# AudioMega_HaGeHa_SMD_v101.net
KiCad netlist of a schematic drawn in EAGLE
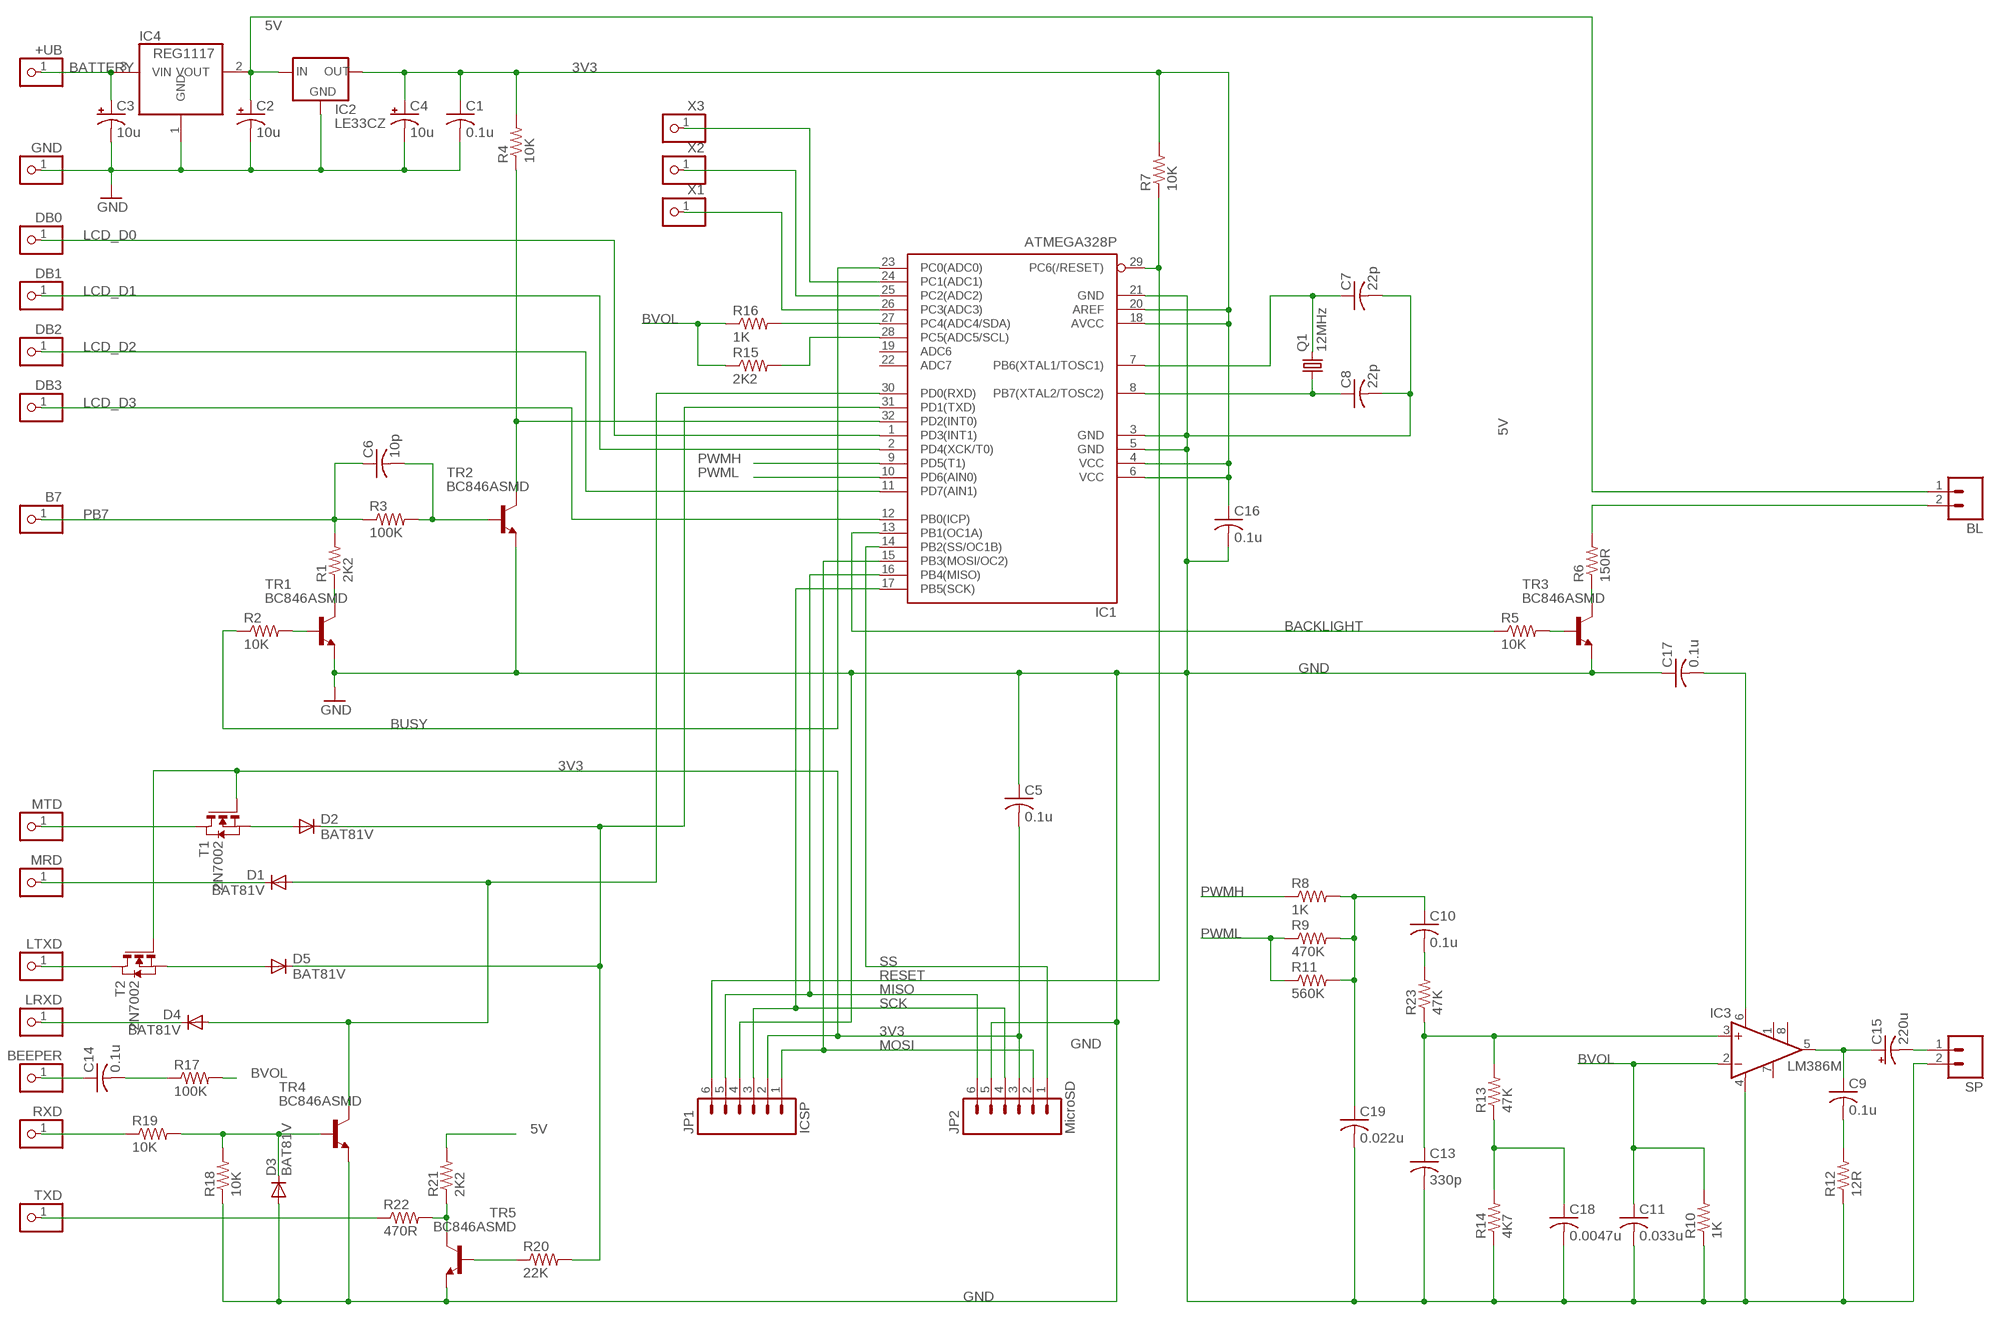
[diagram p0: schematic, sheet 1]

(export (version "E")
  (design (tool "Eeschema 10.0.6"))
  (components
    (comp (ref "+UB")
      (value "PINHD-1X1")
      (footprint "eagle-import:1X01")
      (libsource (lib "eagle-import") (part "PINHD-1X1"))
    )
    (comp (ref "B7")
      (value "PINHD-1X1")
      (footprint "eagle-import:1X01")
      (libsource (lib "eagle-import") (part "PINHD-1X1"))
    )
    (comp (ref "BEEPER")
      (value "PINHD-1X1")
      (footprint "eagle-import:1X01")
      (libsource (lib "eagle-import") (part "PINHD-1X1"))
    )
    (comp (ref "BL")
      (value "M02PTH")
      (footprint "eagle-import:1X02")
      (libsource (lib "eagle-import") (part "M02PTH"))
    )
    (comp (ref "C1")
      (value "0.1u")
      (footprint "eagle-import:C1206")
      (libsource (lib "eagle-import") (part "C-USC1206"))
    )
    (comp (ref "C2")
      (value "10u")
      (footprint "eagle-import:A_3216-18R")
      (libsource (lib "eagle-import") (part "CPOL-USA/3216-18R"))
    )
    (comp (ref "C3")
      (value "10u")
      (footprint "eagle-import:A_3216-18R")
      (libsource (lib "eagle-import") (part "CPOL-USA/3216-18R"))
    )
    (comp (ref "C4")
      (value "10u")
      (footprint "eagle-import:A_3216-18R")
      (libsource (lib "eagle-import") (part "CPOL-USA/3216-18R"))
    )
    (comp (ref "C5")
      (value "0.1u")
      (footprint "eagle-import:C1206")
      (libsource (lib "eagle-import") (part "C-USC1206"))
    )
    (comp (ref "C6")
      (value "10p")
      (footprint "eagle-import:C1206")
      (libsource (lib "eagle-import") (part "C-USC1206"))
    )
    (comp (ref "C7")
      (value "22p")
      (footprint "eagle-import:C1206")
      (libsource (lib "eagle-import") (part "C-USC1206"))
    )
    (comp (ref "C8")
      (value "22p")
      (footprint "eagle-import:C1206")
      (libsource (lib "eagle-import") (part "C-USC1206"))
    )
    (comp (ref "C9")
      (value "0.1u")
      (footprint "eagle-import:C1206")
      (libsource (lib "eagle-import") (part "C-USC1206"))
    )
    (comp (ref "C10")
      (value "0.1u")
      (footprint "eagle-import:C1206")
      (libsource (lib "eagle-import") (part "C-USC1206"))
    )
    (comp (ref "C11")
      (value "0.033u")
      (footprint "eagle-import:C1206")
      (libsource (lib "eagle-import") (part "C-USC1206"))
    )
    (comp (ref "C13")
      (value "330p")
      (footprint "eagle-import:C1206")
      (libsource (lib "eagle-import") (part "C-USC1206"))
    )
    (comp (ref "C14")
      (value "0.1u")
      (footprint "eagle-import:C1206")
      (libsource (lib "eagle-import") (part "C-USC1206"))
    )
    (comp (ref "C15")
      (value "220u")
      (footprint "eagle-import:CT7343")
      (libsource (lib "eagle-import") (part "CPOL-USCT7343"))
    )
    (comp (ref "C16")
      (value "0.1u")
      (footprint "eagle-import:C1206")
      (libsource (lib "eagle-import") (part "C-USC1206"))
    )
    (comp (ref "C17")
      (value "0.1u")
      (footprint "eagle-import:C1206")
      (libsource (lib "eagle-import") (part "C-USC1206"))
    )
    (comp (ref "C18")
      (value "0.0047u")
      (footprint "eagle-import:C1206")
      (libsource (lib "eagle-import") (part "C-USC1206"))
    )
    (comp (ref "C19")
      (value "0.022u")
      (footprint "eagle-import:C1206")
      (libsource (lib "eagle-import") (part "C-USC1206"))
    )
    (comp (ref "D1")
      (value "BAT81V")
      (footprint "eagle-import:SOD123")
      (libsource (lib "eagle-import") (part "DIODE-SOD123"))
    )
    (comp (ref "D2")
      (value "BAT81V")
      (footprint "eagle-import:SOD123")
      (libsource (lib "eagle-import") (part "DIODE-SOD123"))
    )
    (comp (ref "D3")
      (value "BAT81V")
      (footprint "eagle-import:SOD123")
      (libsource (lib "eagle-import") (part "DIODE-SOD123"))
    )
    (comp (ref "D4")
      (value "BAT81V")
      (footprint "eagle-import:SOD123")
      (libsource (lib "eagle-import") (part "DIODE-SOD123"))
    )
    (comp (ref "D5")
      (value "BAT81V")
      (footprint "eagle-import:SOD123")
      (libsource (lib "eagle-import") (part "DIODE-SOD123"))
    )
    (comp (ref "DB0")
      (value "PINHD-1X1")
      (footprint "eagle-import:1X01")
      (libsource (lib "eagle-import") (part "PINHD-1X1"))
    )
    (comp (ref "DB1")
      (value "PINHD-1X1")
      (footprint "eagle-import:1X01")
      (libsource (lib "eagle-import") (part "PINHD-1X1"))
    )
    (comp (ref "DB2")
      (value "PINHD-1X1")
      (footprint "eagle-import:1X01")
      (libsource (lib "eagle-import") (part "PINHD-1X1"))
    )
    (comp (ref "DB3")
      (value "PINHD-1X1")
      (footprint "eagle-import:1X01")
      (libsource (lib "eagle-import") (part "PINHD-1X1"))
    )
    (comp (ref "GND")
      (value "PINHD-1X1")
      (footprint "eagle-import:1X01")
      (libsource (lib "eagle-import") (part "PINHD-1X1"))
    )
    (comp (ref "IC1")
      (value "ATMEGA328P")
      (footprint "eagle-import:TQFP32-08")
      (fields
        (field (name "MPN") "ATMEGA8-16AU")
        (field (name "MPN_1") "ATMEGA8-16AU")
        (field (name "OC_FARNELL") "9171371")
        (field (name "OC_NEWARK") "73M8863")
      )
      (libsource (lib "eagle-import") (part "MEGA8-AI"))
    )
    (comp (ref "IC2")
      (value "LE33CZ")
      (footprint "eagle-import:SOT23")
      (libsource (lib "eagle-import") (part "XC63FPM"))
    )
    (comp (ref "IC3")
      (value "LM386M")
      (footprint "eagle-import:SO08")
      (libsource (lib "eagle-import") (part "LM386?-M1"))
    )
    (comp (ref "IC4")
      (value "REG1117")
      (footprint "eagle-import:SOT223")
      (libsource (lib "eagle-import") (part "REG1117"))
    )
    (comp (ref "JP1")
      (value "ICSP")
      (footprint "eagle-import:1X06")
      (libsource (lib "eagle-import") (part "M06SIP"))
    )
    (comp (ref "JP2")
      (value "MicroSD")
      (footprint "eagle-import:1X06")
      (libsource (lib "eagle-import") (part "M06SIP"))
    )
    (comp (ref "LRXD")
      (value "PINHD-1X1")
      (footprint "eagle-import:1X01")
      (libsource (lib "eagle-import") (part "PINHD-1X1"))
    )
    (comp (ref "LTXD")
      (value "PINHD-1X1")
      (footprint "eagle-import:1X01")
      (libsource (lib "eagle-import") (part "PINHD-1X1"))
    )
    (comp (ref "MRD")
      (value "PINHD-1X1")
      (footprint "eagle-import:1X01")
      (libsource (lib "eagle-import") (part "PINHD-1X1"))
    )
    (comp (ref "MTD")
      (value "PINHD-1X1")
      (footprint "eagle-import:1X01")
      (libsource (lib "eagle-import") (part "PINHD-1X1"))
    )
    (comp (ref "Q1")
      (value "12MHz")
      (footprint "eagle-import:CRYSTAL-SMD-5X3")
      (libsource (lib "eagle-import") (part "CRYSTAL5X3"))
    )
    (comp (ref "R1")
      (value "2K2")
      (footprint "eagle-import:R1206")
      (libsource (lib "eagle-import") (part "R-US_R1206"))
    )
    (comp (ref "R2")
      (value "10K")
      (footprint "eagle-import:R1206")
      (libsource (lib "eagle-import") (part "R-US_R1206"))
    )
    (comp (ref "R3")
      (value "100K")
      (footprint "eagle-import:R1206")
      (libsource (lib "eagle-import") (part "R-US_R1206"))
    )
    (comp (ref "R4")
      (value "10K")
      (footprint "eagle-import:R1206")
      (libsource (lib "eagle-import") (part "R-US_R1206"))
    )
    (comp (ref "R5")
      (value "10K")
      (footprint "eagle-import:R1206")
      (libsource (lib "eagle-import") (part "R-US_R1206"))
    )
    (comp (ref "R6")
      (value "150R")
      (footprint "eagle-import:R1206")
      (libsource (lib "eagle-import") (part "R-US_R1206"))
    )
    (comp (ref "R7")
      (value "10K")
      (footprint "eagle-import:R1206")
      (libsource (lib "eagle-import") (part "R-US_R1206"))
    )
    (comp (ref "R8")
      (value "1K")
      (footprint "eagle-import:R1206")
      (libsource (lib "eagle-import") (part "R-US_R1206"))
    )
    (comp (ref "R9")
      (value "470K")
      (footprint "eagle-import:R1206")
      (libsource (lib "eagle-import") (part "R-US_R1206"))
    )
    (comp (ref "R10")
      (value "1K")
      (footprint "eagle-import:R1206")
      (libsource (lib "eagle-import") (part "R-US_R1206"))
    )
    (comp (ref "R11")
      (value "560K")
      (footprint "eagle-import:R1206")
      (libsource (lib "eagle-import") (part "R-US_R1206"))
    )
    (comp (ref "R12")
      (value "12R")
      (footprint "eagle-import:R1206")
      (libsource (lib "eagle-import") (part "R-US_R1206"))
    )
    (comp (ref "R13")
      (value "47K")
      (footprint "eagle-import:R1206")
      (libsource (lib "eagle-import") (part "R-US_R1206"))
    )
    (comp (ref "R14")
      (value "4K7")
      (footprint "eagle-import:R1206")
      (libsource (lib "eagle-import") (part "R-US_R1206"))
    )
    (comp (ref "R15")
      (value "2K2")
      (footprint "eagle-import:R1206")
      (libsource (lib "eagle-import") (part "R-US_R1206"))
    )
    (comp (ref "R16")
      (value "1K")
      (footprint "eagle-import:R1206")
      (libsource (lib "eagle-import") (part "R-US_R1206"))
    )
    (comp (ref "R17")
      (value "100K")
      (footprint "eagle-import:R1206")
      (libsource (lib "eagle-import") (part "R-US_R1206"))
    )
    (comp (ref "R18")
      (value "10K")
      (footprint "eagle-import:R1206")
      (libsource (lib "eagle-import") (part "R-US_R1206"))
    )
    (comp (ref "R19")
      (value "10K")
      (footprint "eagle-import:R1206")
      (libsource (lib "eagle-import") (part "R-US_R1206"))
    )
    (comp (ref "R20")
      (value "22K")
      (footprint "eagle-import:R1206")
      (libsource (lib "eagle-import") (part "R-US_R1206"))
    )
    (comp (ref "R21")
      (value "2K2")
      (footprint "eagle-import:R1206")
      (libsource (lib "eagle-import") (part "R-US_R1206"))
    )
    (comp (ref "R22")
      (value "470R")
      (footprint "eagle-import:R1206")
      (libsource (lib "eagle-import") (part "R-US_R1206"))
    )
    (comp (ref "R23")
      (value "47K")
      (footprint "eagle-import:R1206")
      (libsource (lib "eagle-import") (part "R-US_R1206"))
    )
    (comp (ref "RXD")
      (value "PINHD-1X1")
      (footprint "eagle-import:1X01")
      (libsource (lib "eagle-import") (part "PINHD-1X1"))
    )
    (comp (ref "SP")
      (value "M02PTH")
      (footprint "eagle-import:1X02")
      (libsource (lib "eagle-import") (part "M02PTH"))
    )
    (comp (ref "T1")
      (value "2N7002")
      (footprint "eagle-import:SOT-23")
      (libsource (lib "eagle-import") (part "NMOSSOT23"))
    )
    (comp (ref "T2")
      (value "2N7002")
      (footprint "eagle-import:SOT-23")
      (libsource (lib "eagle-import") (part "NMOSSOT23"))
    )
    (comp (ref "TR1")
      (value "BC846ASMD")
      (footprint "eagle-import:SOT23")
      (libsource (lib "eagle-import") (part "BC846SMDA"))
    )
    (comp (ref "TR2")
      (value "BC846ASMD")
      (footprint "eagle-import:SOT23")
      (libsource (lib "eagle-import") (part "BC846SMDA"))
    )
    (comp (ref "TR3")
      (value "BC846ASMD")
      (footprint "eagle-import:SOT23")
      (libsource (lib "eagle-import") (part "BC846SMDA"))
    )
    (comp (ref "TR4")
      (value "BC846ASMD")
      (footprint "eagle-import:SOT23")
      (libsource (lib "eagle-import") (part "BC846SMDA"))
    )
    (comp (ref "TR5")
      (value "BC846ASMD")
      (footprint "eagle-import:SOT23")
      (libsource (lib "eagle-import") (part "BC846SMDA"))
    )
    (comp (ref "TXD")
      (value "PINHD-1X1")
      (footprint "eagle-import:1X01")
      (libsource (lib "eagle-import") (part "PINHD-1X1"))
    )
    (comp (ref "X1")
      (value "PINHD-1X1")
      (footprint "eagle-import:1X01")
      (libsource (lib "eagle-import") (part "PINHD-1X1"))
    )
    (comp (ref "X2")
      (value "PINHD-1X1")
      (footprint "eagle-import:1X01")
      (libsource (lib "eagle-import") (part "PINHD-1X1"))
    )
    (comp (ref "X3")
      (value "PINHD-1X1")
      (footprint "eagle-import:1X01")
      (libsource (lib "eagle-import") (part "PINHD-1X1"))
    )
  )
  (nets
    (net (code "1") (name "/3V3") (class "Default")
      (node (ref "C1") (pin "1") (pinfunction "1_1") (pintype "passive"))
      (node (ref "C16") (pin "1") (pinfunction "1_1") (pintype "passive"))
      (node (ref "C4") (pin "+") (pinfunction "+_+") (pintype "passive"))
      (node (ref "C5") (pin "2") (pinfunction "2_2") (pintype "passive"))
      (node (ref "IC1") (pin "18") (pinfunction "AVCC_18") (pintype "power_in"))
      (node (ref "IC1") (pin "20") (pinfunction "AREF_20") (pintype "passive"))
      (node (ref "IC1") (pin "4") (pinfunction "VCC_4") (pintype "power_in"))
      (node (ref "IC1") (pin "6") (pinfunction "VCC_6") (pintype "power_in"))
      (node (ref "IC2") (pin "2") (pinfunction "OUT_2") (pintype "passive"))
      (node (ref "JP1") (pin "2") (pinfunction "2_2") (pintype "passive"))
      (node (ref "JP2") (pin "3") (pinfunction "3_3") (pintype "passive"))
      (node (ref "R4") (pin "2") (pinfunction "2_2") (pintype "passive"))
      (node (ref "R7") (pin "2") (pinfunction "2_2") (pintype "passive"))
      (node (ref "T1") (pin "3") (pinfunction "G_3") (pintype "passive"))
      (node (ref "T2") (pin "3") (pinfunction "G_3") (pintype "passive"))
    )
    (net (code "2") (name "/5V") (class "Default")
      (node (ref "BL") (pin "1") (pinfunction "1_1") (pintype "passive"))
      (node (ref "C2") (pin "+") (pinfunction "+_+") (pintype "passive"))
      (node (ref "IC2") (pin "3") (pinfunction "IN_3") (pintype "input"))
      (node (ref "IC4") (pin "2") (pinfunction "VOUT_2") (pintype "output"))
      (node (ref "R21") (pin "2") (pinfunction "2_2") (pintype "passive"))
    )
    (net (code "3") (name "/BACKLIGHT") (class "Default")
      (node (ref "IC1") (pin "13") (pinfunction "PB1(OC1A)_13") (pintype "bidirectional"))
      (node (ref "R5") (pin "1") (pinfunction "1_1") (pintype "passive"))
    )
    (net (code "4") (name "/BATTERY") (class "Default")
      (node (ref "+UB") (pin "1") (pinfunction "1_1") (pintype "passive"))
      (node (ref "C3") (pin "+") (pinfunction "+_+") (pintype "passive"))
      (node (ref "IC4") (pin "3") (pinfunction "VIN_3") (pintype "input"))
    )
    (net (code "5") (name "/BUSY") (class "Default")
      (node (ref "IC1") (pin "23") (pinfunction "PC0(ADC0)_23") (pintype "bidirectional"))
      (node (ref "R2") (pin "1") (pinfunction "1_1") (pintype "passive"))
    )
    (net (code "6") (name "/BVOL") (class "Default")
      (node (ref "C11") (pin "1") (pinfunction "1_1") (pintype "passive"))
      (node (ref "IC3") (pin "2") (pinfunction "-IN_2") (pintype "input"))
      (node (ref "R10") (pin "2") (pinfunction "2_2") (pintype "passive"))
      (node (ref "R15") (pin "1") (pinfunction "1_1") (pintype "passive"))
      (node (ref "R16") (pin "1") (pinfunction "1_1") (pintype "passive"))
      (node (ref "R17") (pin "2") (pinfunction "2_2") (pintype "passive"))
    )
    (net (code "7") (name "/LCD_D0") (class "Default")
      (node (ref "DB0") (pin "1") (pinfunction "1_1") (pintype "passive"))
      (node (ref "IC1") (pin "1") (pinfunction "PD3(INT1)_1") (pintype "bidirectional"))
    )
    (net (code "8") (name "/LCD_D1") (class "Default")
      (node (ref "DB1") (pin "1") (pinfunction "1_1") (pintype "passive"))
      (node (ref "IC1") (pin "2") (pinfunction "PD4(XCK/T0)_2") (pintype "bidirectional"))
    )
    (net (code "9") (name "/LCD_D2") (class "Default")
      (node (ref "DB2") (pin "1") (pinfunction "1_1") (pintype "passive"))
      (node (ref "IC1") (pin "11") (pinfunction "PD7(AIN1)_11") (pintype "bidirectional"))
    )
    (net (code "10") (name "/LCD_D3") (class "Default")
      (node (ref "DB3") (pin "1") (pinfunction "1_1") (pintype "passive"))
      (node (ref "IC1") (pin "12") (pinfunction "PB0(ICP)_12") (pintype "bidirectional"))
    )
    (net (code "11") (name "/MISO") (class "Default")
      (node (ref "IC1") (pin "16") (pinfunction "PB4(MISO)_16") (pintype "bidirectional"))
      (node (ref "JP1") (pin "5") (pinfunction "5_5") (pintype "passive"))
      (node (ref "JP2") (pin "6") (pinfunction "6_6") (pintype "passive"))
    )
    (net (code "12") (name "/MOSI") (class "Default")
      (node (ref "IC1") (pin "15") (pinfunction "PB3(MOSI/OC2)_15") (pintype "bidirectional"))
      (node (ref "JP1") (pin "1") (pinfunction "1_1") (pintype "passive"))
      (node (ref "JP2") (pin "2") (pinfunction "2_2") (pintype "passive"))
    )
    (net (code "13") (name "/PB7") (class "Default")
      (node (ref "B7") (pin "1") (pinfunction "1_1") (pintype "passive"))
      (node (ref "C6") (pin "1") (pinfunction "1_1") (pintype "passive"))
      (node (ref "R1") (pin "2") (pinfunction "2_2") (pintype "passive"))
      (node (ref "R3") (pin "1") (pinfunction "1_1") (pintype "passive"))
    )
    (net (code "14") (name "/PWMH") (class "Default")
      (node (ref "IC1") (pin "9") (pinfunction "PD5(T1)_9") (pintype "bidirectional"))
      (node (ref "R8") (pin "1") (pinfunction "1_1") (pintype "passive"))
    )
    (net (code "15") (name "/PWML") (class "Default")
      (node (ref "IC1") (pin "10") (pinfunction "PD6(AIN0)_10") (pintype "bidirectional"))
      (node (ref "R11") (pin "1") (pinfunction "1_1") (pintype "passive"))
      (node (ref "R9") (pin "1") (pinfunction "1_1") (pintype "passive"))
    )
    (net (code "16") (name "/RESET") (class "Default")
      (node (ref "IC1") (pin "29") (pinfunction "PC6(/RESET)_29") (pintype "bidirectional"))
      (node (ref "JP1") (pin "6") (pinfunction "6_6") (pintype "passive"))
      (node (ref "R7") (pin "1") (pinfunction "1_1") (pintype "passive"))
    )
    (net (code "17") (name "/SCK") (class "Default")
      (node (ref "IC1") (pin "17") (pinfunction "PB5(SCK)_17") (pintype "bidirectional"))
      (node (ref "JP1") (pin "3") (pinfunction "3_3") (pintype "passive"))
      (node (ref "JP2") (pin "4") (pinfunction "4_4") (pintype "passive"))
    )
    (net (code "18") (name "/SS") (class "Default")
      (node (ref "IC1") (pin "14") (pinfunction "PB2(SS/OC1B)_14") (pintype "bidirectional"))
      (node (ref "JP2") (pin "1") (pinfunction "1_1") (pintype "passive"))
    )
    (net (code "19") (name "GND") (class "Default")
      (node (ref "C1") (pin "2") (pinfunction "2_2") (pintype "passive"))
      (node (ref "C11") (pin "2") (pinfunction "2_2") (pintype "passive"))
      (node (ref "C13") (pin "2") (pinfunction "2_2") (pintype "passive"))
      (node (ref "C16") (pin "2") (pinfunction "2_2") (pintype "passive"))
      (node (ref "C17") (pin "1") (pinfunction "1_1") (pintype "passive"))
      (node (ref "C18") (pin "2") (pinfunction "2_2") (pintype "passive"))
      (node (ref "C19") (pin "2") (pinfunction "2_2") (pintype "passive"))
      (node (ref "C2") (pin "-") (pinfunction "-_-") (pintype "passive"))
      (node (ref "C3") (pin "-") (pinfunction "-_-") (pintype "passive"))
      (node (ref "C4") (pin "-") (pinfunction "-_-") (pintype "passive"))
      (node (ref "C5") (pin "1") (pinfunction "1_1") (pintype "passive"))
      (node (ref "C7") (pin "2") (pinfunction "2_2") (pintype "passive"))
      (node (ref "C8") (pin "2") (pinfunction "2_2") (pintype "passive"))
      (node (ref "D3") (pin "A") (pinfunction "A_A") (pintype "passive"))
      (node (ref "GND") (pin "1") (pinfunction "1_1") (pintype "passive"))
      (node (ref "IC1") (pin "21") (pinfunction "GND_21") (pintype "power_in"))
      (node (ref "IC1") (pin "3") (pinfunction "GND_3") (pintype "power_in"))
      (node (ref "IC1") (pin "5") (pinfunction "GND_5") (pintype "power_in"))
      (node (ref "IC2") (pin "1") (pinfunction "GND_1") (pintype "input"))
      (node (ref "IC3") (pin "4") (pinfunction "GND_4") (pintype "power_in"))
      (node (ref "IC4") (pin "1") (pinfunction "GND_1") (pintype "power_in"))
      (node (ref "JP1") (pin "4") (pinfunction "4_4") (pintype "passive"))
      (node (ref "JP2") (pin "5") (pinfunction "5_5") (pintype "passive"))
      (node (ref "R10") (pin "1") (pinfunction "1_1") (pintype "passive"))
      (node (ref "R12") (pin "1") (pinfunction "1_1") (pintype "passive"))
      (node (ref "R14") (pin "1") (pinfunction "1_1") (pintype "passive"))
      (node (ref "R18") (pin "1") (pinfunction "1_1") (pintype "passive"))
      (node (ref "SP") (pin "2") (pinfunction "2_2") (pintype "passive"))
      (node (ref "TR1") (pin "2") (pinfunction "E_2") (pintype "passive"))
      (node (ref "TR2") (pin "2") (pinfunction "E_2") (pintype "passive"))
      (node (ref "TR3") (pin "2") (pinfunction "E_2") (pintype "passive"))
      (node (ref "TR4") (pin "2") (pinfunction "E_2") (pintype "passive"))
      (node (ref "TR5") (pin "2") (pinfunction "E_2") (pintype "passive"))
    )
    (net (code "20") (name "Net-(BEEPER-Pad1)") (class "Default")
      (node (ref "BEEPER") (pin "1") (pinfunction "1_1") (pintype "passive"))
      (node (ref "C14") (pin "1") (pinfunction "1_1") (pintype "passive"))
    )
    (net (code "21") (name "Net-(BL-Pad2)") (class "Default")
      (node (ref "BL") (pin "2") (pinfunction "2_2") (pintype "passive"))
      (node (ref "R6") (pin "2") (pinfunction "2_2") (pintype "passive"))
    )
    (net (code "22") (name "Net-(C9-Pad2)") (class "Default")
      (node (ref "C9") (pin "2") (pinfunction "2_2") (pintype "passive"))
      (node (ref "R12") (pin "2") (pinfunction "2_2") (pintype "passive"))
    )
    (net (code "23") (name "Net-(C10-Pad1)") (class "Default")
      (node (ref "C10") (pin "1") (pinfunction "1_1") (pintype "passive"))
      (node (ref "C19") (pin "1") (pinfunction "1_1") (pintype "passive"))
      (node (ref "R11") (pin "2") (pinfunction "2_2") (pintype "passive"))
      (node (ref "R8") (pin "2") (pinfunction "2_2") (pintype "passive"))
      (node (ref "R9") (pin "2") (pinfunction "2_2") (pintype "passive"))
    )
    (net (code "24") (name "Net-(C10-Pad2)") (class "Default")
      (node (ref "C10") (pin "2") (pinfunction "2_2") (pintype "passive"))
      (node (ref "R23") (pin "2") (pinfunction "2_2") (pintype "passive"))
    )
    (net (code "25") (name "Net-(C14-Pad2)") (class "Default")
      (node (ref "C14") (pin "2") (pinfunction "2_2") (pintype "passive"))
      (node (ref "R17") (pin "1") (pinfunction "1_1") (pintype "passive"))
    )
    (net (code "26") (name "Net-(C15-Pad-)") (class "Default")
      (node (ref "C15") (pin "-") (pinfunction "-_-") (pintype "passive"))
      (node (ref "SP") (pin "1") (pinfunction "1_1") (pintype "passive"))
    )
    (net (code "27") (name "Net-(C18-Pad1)") (class "Default")
      (node (ref "C18") (pin "1") (pinfunction "1_1") (pintype "passive"))
      (node (ref "R13") (pin "1") (pinfunction "1_1") (pintype "passive"))
      (node (ref "R14") (pin "2") (pinfunction "2_2") (pintype "passive"))
    )
    (net (code "28") (name "Net-(D1-PadC)") (class "Default")
      (node (ref "D1") (pin "C") (pinfunction "C_C") (pintype "passive"))
      (node (ref "MRD") (pin "1") (pinfunction "1_1") (pintype "passive"))
    )
    (net (code "29") (name "Net-(D4-PadC)") (class "Default")
      (node (ref "D4") (pin "C") (pinfunction "C_C") (pintype "passive"))
      (node (ref "LRXD") (pin "1") (pinfunction "1_1") (pintype "passive"))
    )
    (net (code "30") (name "Net-(IC1-PB6(XTAL1{slash}TOSC1))") (class "Default")
      (node (ref "C7") (pin "1") (pinfunction "1_1") (pintype "passive"))
      (node (ref "IC1") (pin "7") (pinfunction "PB6(XTAL1/TOSC1)_7") (pintype "bidirectional"))
      (node (ref "Q1") (pin "3") (pinfunction "2_3") (pintype "passive"))
    )
    (net (code "31") (name "Net-(IC1-PB7(XTAL2{slash}TOSC2))") (class "Default")
      (node (ref "C8") (pin "1") (pinfunction "1_1") (pintype "passive"))
      (node (ref "IC1") (pin "8") (pinfunction "PB7(XTAL2/TOSC2)_8") (pintype "bidirectional"))
      (node (ref "Q1") (pin "1") (pinfunction "1_1") (pintype "passive"))
    )
    (net (code "32") (name "Net-(IC1-PC1(ADC1))") (class "Default")
      (node (ref "IC1") (pin "24") (pinfunction "PC1(ADC1)_24") (pintype "bidirectional"))
      (node (ref "X3") (pin "1") (pinfunction "1_1") (pintype "passive"))
    )
    (net (code "33") (name "Net-(IC1-PC2(ADC2))") (class "Default")
      (node (ref "IC1") (pin "25") (pinfunction "PC2(ADC2)_25") (pintype "bidirectional"))
      (node (ref "X2") (pin "1") (pinfunction "1_1") (pintype "passive"))
    )
    (net (code "34") (name "Net-(IC1-PC3(ADC3))") (class "Default")
      (node (ref "IC1") (pin "26") (pinfunction "PC3(ADC3)_26") (pintype "bidirectional"))
      (node (ref "X1") (pin "1") (pinfunction "1_1") (pintype "passive"))
    )
    (net (code "35") (name "Net-(IC1-PC4(ADC4{slash}SDA))") (class "Default")
      (node (ref "IC1") (pin "27") (pinfunction "PC4(ADC4/SDA)_27") (pintype "bidirectional"))
      (node (ref "R16") (pin "2") (pinfunction "2_2") (pintype "passive"))
    )
    (net (code "36") (name "Net-(IC1-PC5(ADC5{slash}SCL))") (class "Default")
      (node (ref "IC1") (pin "28") (pinfunction "PC5(ADC5/SCL)_28") (pintype "bidirectional"))
      (node (ref "R15") (pin "2") (pinfunction "2_2") (pintype "passive"))
    )
    (net (code "37") (name "Net-(IC1-PD0(RXD))") (class "Default")
      (node (ref "D1") (pin "A") (pinfunction "A_A") (pintype "passive"))
      (node (ref "D4") (pin "A") (pinfunction "A_A") (pintype "passive"))
      (node (ref "IC1") (pin "30") (pinfunction "PD0(RXD)_30") (pintype "bidirectional"))
      (node (ref "TR4") (pin "3") (pinfunction "C_3") (pintype "passive"))
    )
    (net (code "38") (name "Net-(IC1-PD1(TXD))") (class "Default")
      (node (ref "D2") (pin "C") (pinfunction "C_C") (pintype "passive"))
      (node (ref "D5") (pin "C") (pinfunction "C_C") (pintype "passive"))
      (node (ref "IC1") (pin "31") (pinfunction "PD1(TXD)_31") (pintype "bidirectional"))
      (node (ref "R20") (pin "2") (pinfunction "2_2") (pintype "passive"))
    )
    (net (code "39") (name "Net-(IC1-PD2(INT0))") (class "Default")
      (node (ref "IC1") (pin "32") (pinfunction "PD2(INT0)_32") (pintype "bidirectional"))
      (node (ref "R4") (pin "1") (pinfunction "1_1") (pintype "passive"))
      (node (ref "TR2") (pin "3") (pinfunction "C_3") (pintype "passive"))
    )
    (net (code "40") (name "Net-(IC3-+IN)") (class "Default")
      (node (ref "C13") (pin "1") (pinfunction "1_1") (pintype "passive"))
      (node (ref "IC3") (pin "3") (pinfunction "+IN_3") (pintype "input"))
      (node (ref "R13") (pin "2") (pinfunction "2_2") (pintype "passive"))
      (node (ref "R23") (pin "1") (pinfunction "1_1") (pintype "passive"))
    )
    (net (code "41") (name "Net-(IC3-OUT)") (class "Default")
      (node (ref "C15") (pin "+") (pinfunction "+_+") (pintype "passive"))
      (node (ref "C9") (pin "1") (pinfunction "1_1") (pintype "passive"))
      (node (ref "IC3") (pin "5") (pinfunction "OUT_5") (pintype "output"))
    )
    (net (code "42") (name "Net-(IC3-VS)") (class "Default")
      (node (ref "C17") (pin "2") (pinfunction "2_2") (pintype "passive"))
      (node (ref "IC3") (pin "6") (pinfunction "VS_6") (pintype "power_in"))
    )
    (net (code "43") (name "Net-(R19-Pad1)") (class "Default")
      (node (ref "R19") (pin "1") (pinfunction "1_1") (pintype "passive"))
      (node (ref "RXD") (pin "1") (pinfunction "1_1") (pintype "passive"))
    )
    (net (code "44") (name "Net-(R22-Pad1)") (class "Default")
      (node (ref "R22") (pin "1") (pinfunction "1_1") (pintype "passive"))
      (node (ref "TXD") (pin "1") (pinfunction "1_1") (pintype "passive"))
    )
    (net (code "45") (name "Net-(T1-D)") (class "Default")
      (node (ref "MTD") (pin "1") (pinfunction "1_1") (pintype "passive"))
      (node (ref "T1") (pin "1") (pinfunction "D_1") (pintype "passive"))
    )
    (net (code "46") (name "Net-(T1-S)") (class "Default")
      (node (ref "D2") (pin "A") (pinfunction "A_A") (pintype "passive"))
      (node (ref "T1") (pin "2") (pinfunction "S_2") (pintype "passive"))
    )
    (net (code "47") (name "Net-(T2-D)") (class "Default")
      (node (ref "LTXD") (pin "1") (pinfunction "1_1") (pintype "passive"))
      (node (ref "T2") (pin "1") (pinfunction "D_1") (pintype "passive"))
    )
    (net (code "48") (name "Net-(T2-S)") (class "Default")
      (node (ref "D5") (pin "A") (pinfunction "A_A") (pintype "passive"))
      (node (ref "T2") (pin "2") (pinfunction "S_2") (pintype "passive"))
    )
    (net (code "49") (name "Net-(TR1-B)") (class "Default")
      (node (ref "R2") (pin "2") (pinfunction "2_2") (pintype "passive"))
      (node (ref "TR1") (pin "1") (pinfunction "B_1") (pintype "passive"))
    )
    (net (code "50") (name "Net-(TR1-C)") (class "Default")
      (node (ref "R1") (pin "1") (pinfunction "1_1") (pintype "passive"))
      (node (ref "TR1") (pin "3") (pinfunction "C_3") (pintype "passive"))
    )
    (net (code "51") (name "Net-(TR2-B)") (class "Default")
      (node (ref "C6") (pin "2") (pinfunction "2_2") (pintype "passive"))
      (node (ref "R3") (pin "2") (pinfunction "2_2") (pintype "passive"))
      (node (ref "TR2") (pin "1") (pinfunction "B_1") (pintype "passive"))
    )
    (net (code "52") (name "Net-(TR3-B)") (class "Default")
      (node (ref "R5") (pin "2") (pinfunction "2_2") (pintype "passive"))
      (node (ref "TR3") (pin "1") (pinfunction "B_1") (pintype "passive"))
    )
    (net (code "53") (name "Net-(TR3-C)") (class "Default")
      (node (ref "R6") (pin "1") (pinfunction "1_1") (pintype "passive"))
      (node (ref "TR3") (pin "3") (pinfunction "C_3") (pintype "passive"))
    )
    (net (code "54") (name "Net-(TR4-B)") (class "Default")
      (node (ref "D3") (pin "C") (pinfunction "C_C") (pintype "passive"))
      (node (ref "R18") (pin "2") (pinfunction "2_2") (pintype "passive"))
      (node (ref "R19") (pin "2") (pinfunction "2_2") (pintype "passive"))
      (node (ref "TR4") (pin "1") (pinfunction "B_1") (pintype "passive"))
    )
    (net (code "55") (name "Net-(TR5-B)") (class "Default")
      (node (ref "R20") (pin "1") (pinfunction "1_1") (pintype "passive"))
      (node (ref "TR5") (pin "1") (pinfunction "B_1") (pintype "passive"))
    )
    (net (code "56") (name "Net-(TR5-C)") (class "Default")
      (node (ref "R21") (pin "1") (pinfunction "1_1") (pintype "passive"))
      (node (ref "R22") (pin "2") (pinfunction "2_2") (pintype "passive"))
      (node (ref "TR5") (pin "3") (pinfunction "C_3") (pintype "passive"))
    )
    (net (code "57") (name "unconnected-(IC1-ADC6-Pad19)") (class "Default")
      (node (ref "IC1") (pin "19") (pinfunction "ADC6_19") (pintype "bidirectional"))
    )
    (net (code "58") (name "unconnected-(IC1-ADC7-Pad22)") (class "Default")
      (node (ref "IC1") (pin "22") (pinfunction "ADC7_22") (pintype "bidirectional"))
    )
    (net (code "59") (name "unconnected-(IC3-BYPASS-Pad7)") (class "Default")
      (node (ref "IC3") (pin "7") (pinfunction "BYPASS_7") (pintype "passive"))
    )
    (net (code "60") (name "unconnected-(IC3-GAIN-Pad1)") (class "Default")
      (node (ref "IC3") (pin "1") (pinfunction "GAIN_1") (pintype "passive"))
    )
    (net (code "61") (name "unconnected-(IC3-GAIN-Pad8)") (class "Default")
      (node (ref "IC3") (pin "8") (pinfunction "GAIN_8") (pintype "passive"))
    )
  )
)
